# Lab11_445L.net
KiCad netlist of a schematic drawn in EAGLE
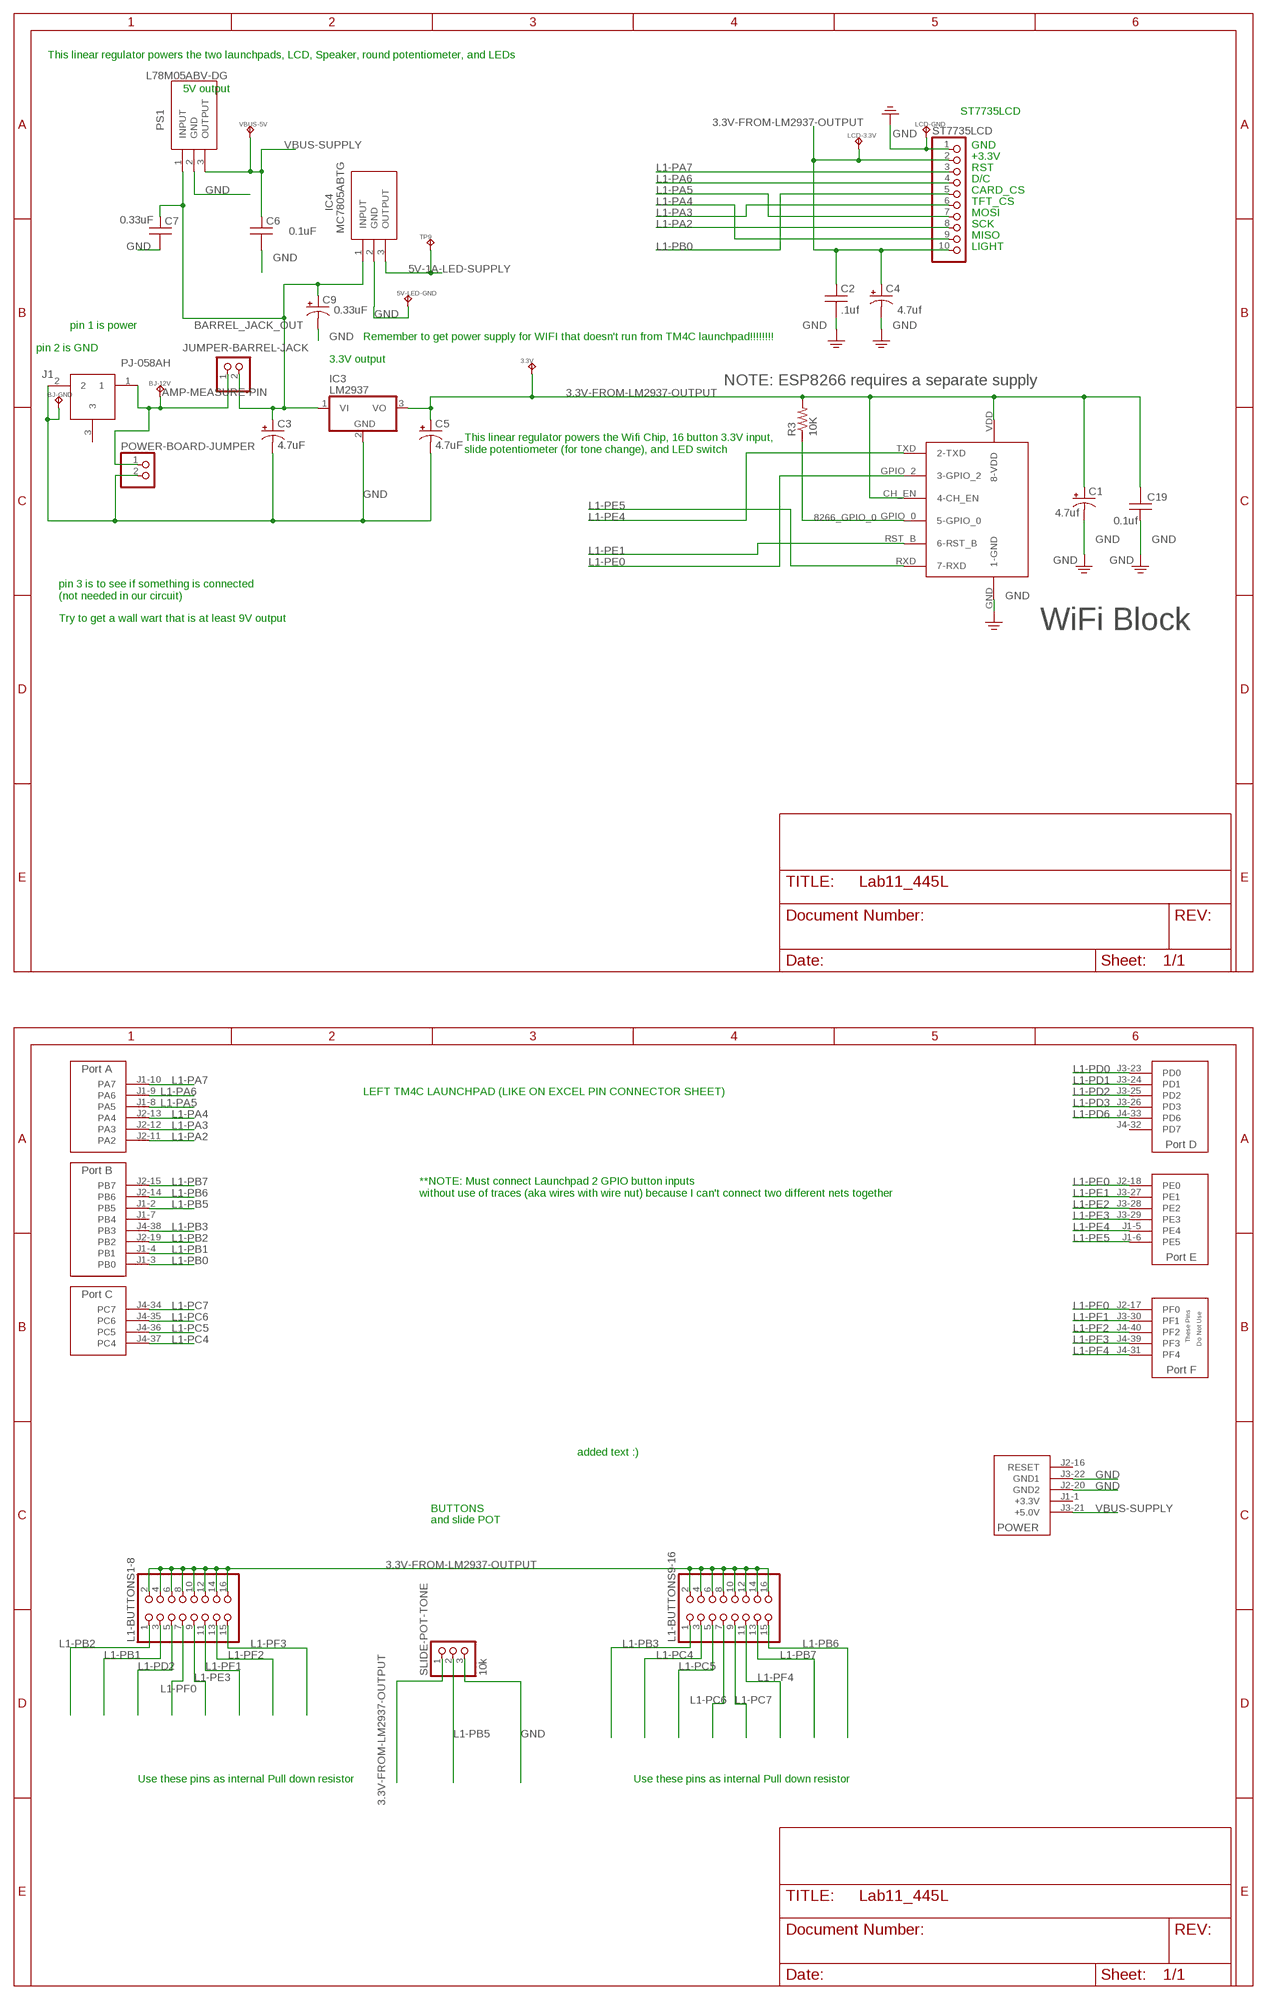
[diagram p0: schematic, sheet 1, part 1 of 2]
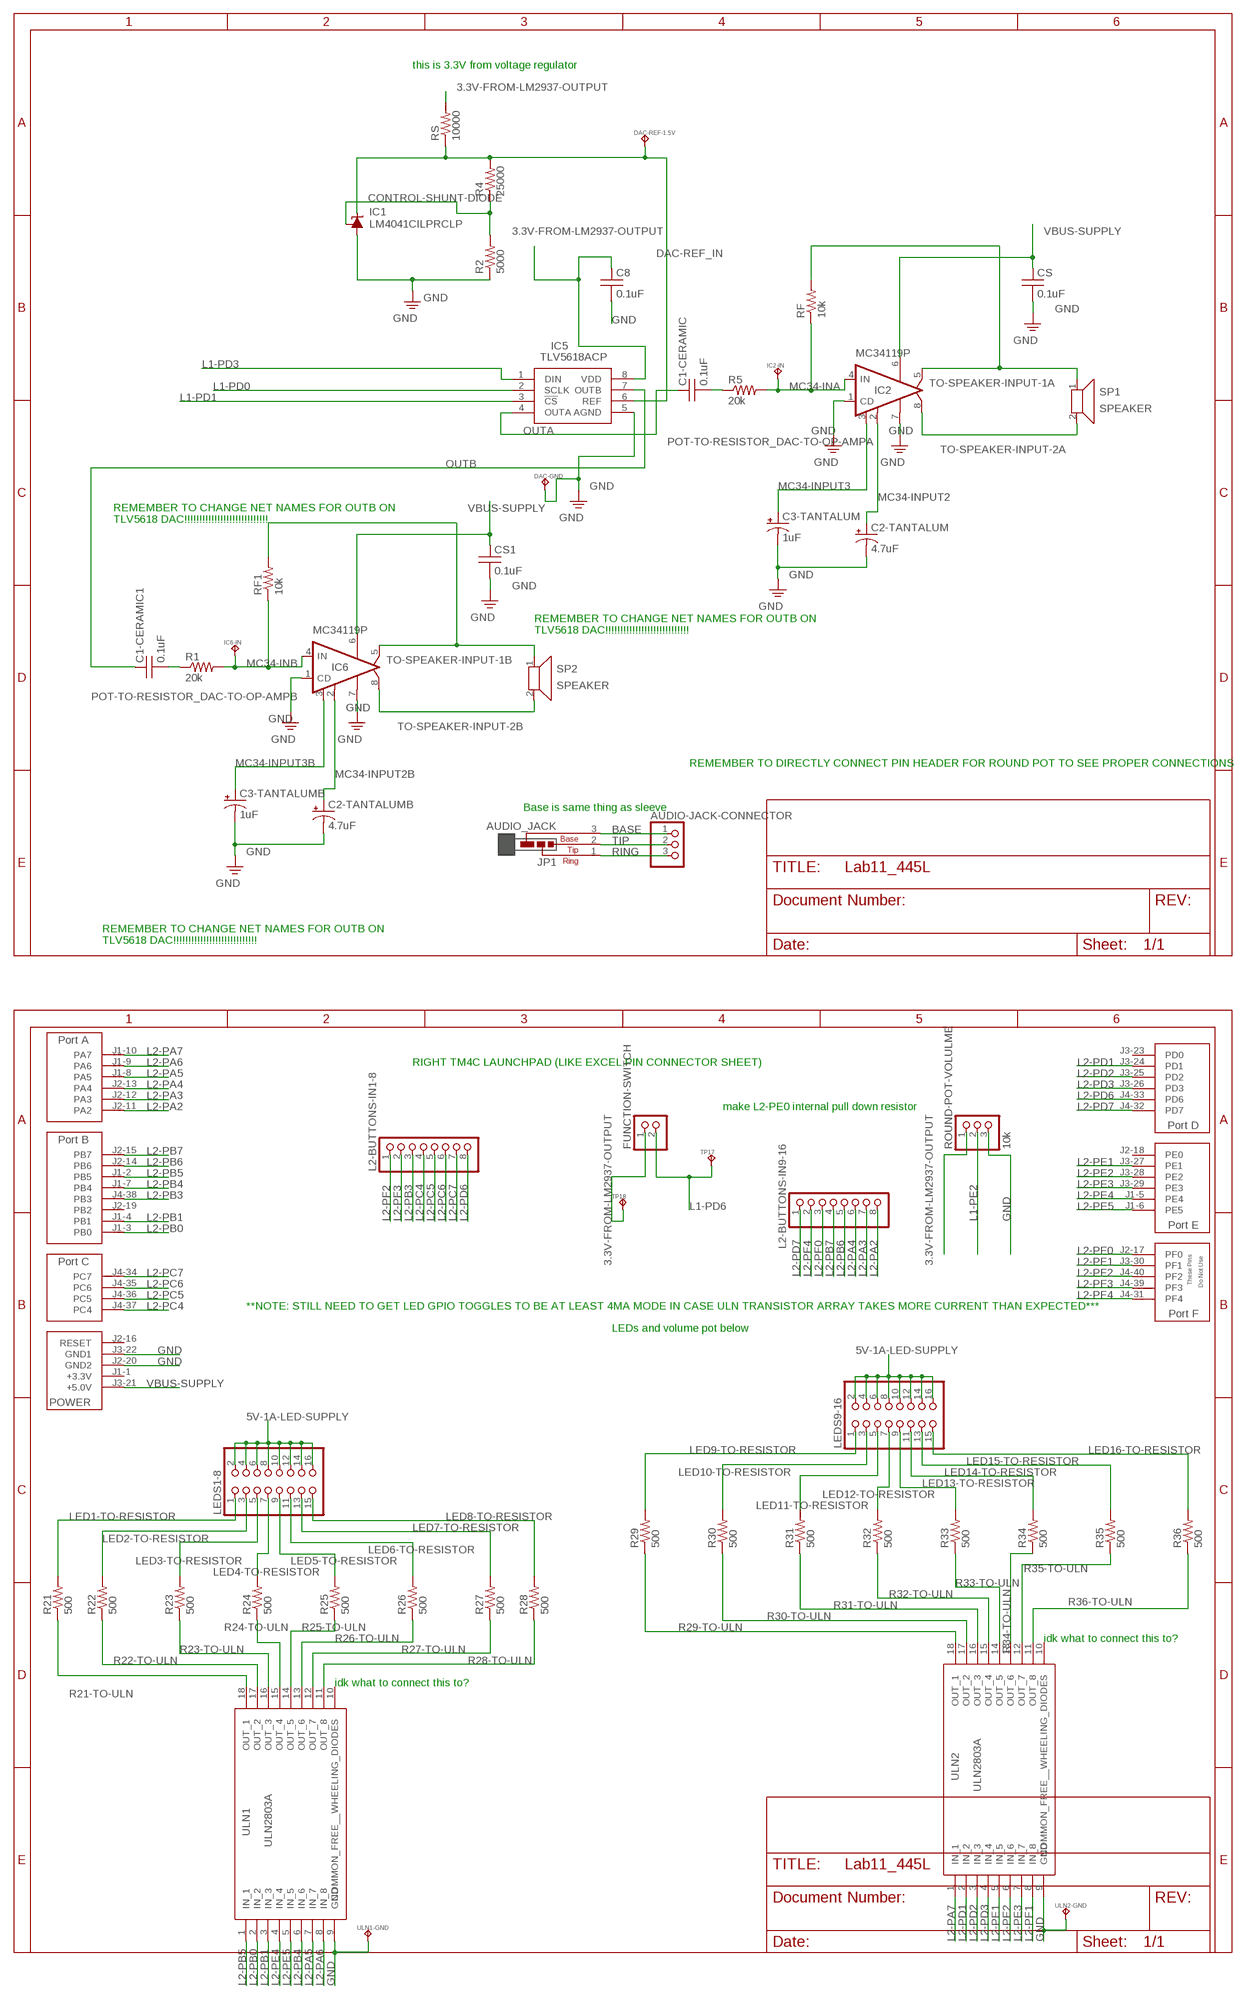
[diagram p1: schematic, sheet 1, part 2 of 2]

(export (version "E")
  (design (tool "Eeschema 10.0.6"))
  (components
    (comp (ref "3.3V")
      (value "TP_KEYSTONE500X")
      (footprint "eagle-import:P1.1MM")
      (libsource (lib "eagle-import") (part "TP_KEYSTONE500X"))
    )
    (comp (ref "5V-LED-GND")
      (value "TP_KEYSTONE500X")
      (footprint "eagle-import:P1.1MM")
      (libsource (lib "eagle-import") (part "TP_KEYSTONE500X"))
    )
    (comp (ref "AMP-MEASURE-PIN")
      (value "PINHD-1X2")
      (footprint "eagle-import:1X02")
      (libsource (lib "eagle-import") (part "PINHD-1X2"))
    )
    (comp (ref "AUDIO-JACK-CONNECTOR")
      (value "PINHD-1X3")
      (footprint "eagle-import:1X03")
      (libsource (lib "eagle-import") (part "PINHD-1X3"))
    )
    (comp (ref "BJ-12V")
      (value "TP_KEYSTONE500X")
      (footprint "eagle-import:P1.1MM")
      (libsource (lib "eagle-import") (part "TP_KEYSTONE500X"))
    )
    (comp (ref "BJ-GND")
      (value "TP_KEYSTONE500X")
      (footprint "eagle-import:P1.1MM")
      (libsource (lib "eagle-import") (part "TP_KEYSTONE500X"))
    )
    (comp (ref "C1")
      (value "4.7uf")
      (footprint "eagle-import:CAP200MILPOLARIZED")
      (libsource (lib "eagle-import") (part "CAPACITOR_POLARIZEDE5-6"))
    )
    (comp (ref "C1-CERAMIC")
      (value "0.1uF")
      (footprint "eagle-import:CAP100MIL")
      (libsource (lib "eagle-import") (part "CAPACITOR025-024X044"))
    )
    (comp (ref "C1-CERAMIC1")
      (value "0.1uF")
      (footprint "eagle-import:CAP100MIL")
      (libsource (lib "eagle-import") (part "CAPACITOR025-024X044"))
    )
    (comp (ref "C2")
      (value ".1uf")
      (footprint "eagle-import:CAP200MIL")
      (libsource (lib "eagle-import") (part "CAPACITOR050-024X044"))
    )
    (comp (ref "C2-TANTALUM")
      (value "4.7uF")
      (footprint "eagle-import:CAP200MILPOLARIZED")
      (libsource (lib "eagle-import") (part "CAPACITOR_POLARIZEDE5-6"))
    )
    (comp (ref "C2-TANTALUMB")
      (value "4.7uF")
      (footprint "eagle-import:CAP200MILPOLARIZED")
      (libsource (lib "eagle-import") (part "CAPACITOR_POLARIZEDE5-6"))
    )
    (comp (ref "C3")
      (value "4.7uF")
      (footprint "eagle-import:CAP200MILPOLARIZED")
      (libsource (lib "eagle-import") (part "CAPACITOR_POLARIZEDE5-6"))
    )
    (comp (ref "C3-TANTALUM")
      (value "1uF")
      (footprint "eagle-import:CAP200MILPOLARIZED")
      (libsource (lib "eagle-import") (part "CAPACITOR_POLARIZEDE5-6"))
    )
    (comp (ref "C3-TANTALUMB")
      (value "1uF")
      (footprint "eagle-import:CAP200MILPOLARIZED")
      (libsource (lib "eagle-import") (part "CAPACITOR_POLARIZEDE5-6"))
    )
    (comp (ref "C4")
      (value "4.7uf")
      (footprint "eagle-import:CAP200MILPOLARIZED")
      (libsource (lib "eagle-import") (part "CAPACITOR_POLARIZEDE5-6"))
    )
    (comp (ref "C5")
      (value "4.7uF")
      (footprint "eagle-import:CAP200MILPOLARIZED")
      (libsource (lib "eagle-import") (part "CAPACITOR_POLARIZEDE5-6"))
    )
    (comp (ref "C6")
      (value "0.1uF")
      (footprint "eagle-import:CAP200MIL")
      (libsource (lib "eagle-import") (part "CAPACITOR050-024X044"))
    )
    (comp (ref "C7")
      (value "0.33uF")
      (footprint "eagle-import:CAP200MIL")
      (libsource (lib "eagle-import") (part "CAPACITOR050-024X044"))
    )
    (comp (ref "C8")
      (value "0.1uF")
      (footprint "eagle-import:CAP100MIL")
      (libsource (lib "eagle-import") (part "CAPACITOR025-024X044"))
    )
    (comp (ref "C9")
      (value "0.33uF")
      (footprint "eagle-import:CAP200MILPOLARIZED")
      (libsource (lib "eagle-import") (part "CAPACITOR_POLARIZEDE5-6"))
    )
    (comp (ref "C19")
      (value "0.1uf")
      (footprint "eagle-import:CAP200MIL")
      (libsource (lib "eagle-import") (part "CAPACITOR050-024X044"))
    )
    (comp (ref "CS")
      (value "0.1uF")
      (footprint "eagle-import:CAP100MIL")
      (libsource (lib "eagle-import") (part "CAPACITOR025-024X044"))
    )
    (comp (ref "CS1")
      (value "0.1uF")
      (footprint "eagle-import:CAP100MIL")
      (libsource (lib "eagle-import") (part "CAPACITOR025-024X044"))
    )
    (comp (ref "DAC-GND")
      (value "TP_KEYSTONE500X")
      (footprint "eagle-import:P1.1MM")
      (libsource (lib "eagle-import") (part "TP_KEYSTONE500X"))
    )
    (comp (ref "DAC-REF-1.5V")
      (value "TP_KEYSTONE500X")
      (footprint "eagle-import:P1.1MM")
      (libsource (lib "eagle-import") (part "TP_KEYSTONE500X"))
    )
    (comp (ref "FUNCTION-SWITCH")
      (value "PINHD-1X2")
      (footprint "eagle-import:1X02")
      (libsource (lib "eagle-import") (part "PINHD-1X2"))
    )
    (comp (ref "IC1")
      (value "LM4041CILPRCLP")
      (footprint "eagle-import:LP_O-PBCY-W3")
      (fields (field (name "MPN") "LM4041CILP"))
      (libsource (lib "eagle-import") (part "LM4041CILPRLPC"))
    )
    (comp (ref "IC2")
      (value "MC34119P")
      (footprint "eagle-import:DIL08")
      (libsource (lib "eagle-import") (part "MC34119P"))
    )
    (comp (ref "IC2-IN")
      (value "TP_KEYSTONE500X")
      (footprint "eagle-import:P1.1MM")
      (libsource (lib "eagle-import") (part "TP_KEYSTONE500X"))
    )
    (comp (ref "IC3")
      (value "LM2937")
      (footprint "eagle-import:TO220")
      (libsource (lib "eagle-import") (part "LM2937"))
    )
    (comp (ref "IC4")
      (value "MC7805ABTG")
      (footprint "eagle-import:TO254P482X997X2018-3P")
      (fields (field (name "MOUSER_PART_NUMBER") "863-MC7805ABTG"))
      (libsource (lib "eagle-import") (part "MC7805ABTG"))
    )
    (comp (ref "IC5")
      (value "TLV5618ACP")
      (footprint "eagle-import:DIP794W53P254L959H508Q8N")
      (fields (field (name "MOUSER_PART_NUMBER") "595-TLV5618ACP"))
      (libsource (lib "eagle-import") (part "TLV5618ACP"))
    )
    (comp (ref "IC6")
      (value "MC34119P")
      (footprint "eagle-import:DIL08")
      (libsource (lib "eagle-import") (part "MC34119P"))
    )
    (comp (ref "IC6-IN")
      (value "TP_KEYSTONE500X")
      (footprint "eagle-import:P1.1MM")
      (libsource (lib "eagle-import") (part "TP_KEYSTONE500X"))
    )
    (comp (ref "J1")
      (value "PJ-058AH")
      (footprint "eagle-import:PJ058AH")
      (fields (field (name "MOUSER_PART_NUMBER") "490-PJ-058AH"))
      (libsource (lib "eagle-import") (part "PJ-058AH"))
    )
    (comp (ref "JP1")
      (value "AUDIO_JACK")
      (footprint "eagle-import:JACK")
      (libsource (lib "eagle-import") (part "AUDIO_JACK"))
    )
    (comp (ref "L1-BUTTONS1-8")
      (value "PINHD-2X8")
      (footprint "eagle-import:2X08")
      (libsource (lib "eagle-import") (part "PINHD-2X8"))
    )
    (comp (ref "L1-BUTTONS9-16")
      (value "PINHD-2X8")
      (footprint "eagle-import:2X08")
      (libsource (lib "eagle-import") (part "PINHD-2X8"))
    )
    (comp (ref "L2-BUTTONS-IN1-8")
      (value "PINHD-1X8")
      (footprint "eagle-import:1X08")
      (libsource (lib "eagle-import") (part "PINHD-1X8"))
    )
    (comp (ref "L2-BUTTONS-IN9-16")
      (value "PINHD-1X8")
      (footprint "eagle-import:1X08")
      (libsource (lib "eagle-import") (part "PINHD-1X8"))
    )
    (comp (ref "LCD-3.3V")
      (value "TP_KEYSTONE500X")
      (footprint "eagle-import:P1.1MM")
      (libsource (lib "eagle-import") (part "TP_KEYSTONE500X"))
    )
    (comp (ref "LCD-GND")
      (value "TP_KEYSTONE500X")
      (footprint "eagle-import:P1.1MM")
      (libsource (lib "eagle-import") (part "TP_KEYSTONE500X"))
    )
    (comp (ref "LEDS1-8")
      (value "PINHD-2X8")
      (footprint "eagle-import:2X08")
      (libsource (lib "eagle-import") (part "PINHD-2X8"))
    )
    (comp (ref "LEDS9-16")
      (value "PINHD-2X8")
      (footprint "eagle-import:2X08")
      (libsource (lib "eagle-import") (part "PINHD-2X8"))
    )
    (comp (ref "POWER-BOARD-JUMPER")
      (value "PINHD-1X2")
      (footprint "eagle-import:1X02")
      (libsource (lib "eagle-import") (part "PINHD-1X2"))
    )
    (comp (ref "PS1")
      (value "L78M05ABV-DG")
      (footprint "eagle-import:TO255P460X1020X2008-3P")
      (fields (field (name "MOUSER_PART_NUMBER") "511-L78M05ABV-DG"))
      (libsource (lib "eagle-import") (part "L78M05ABV-DG"))
    )
    (comp (ref "R1")
      (value "20k")
      (footprint "eagle-import:RES200MIL")
      (libsource (lib "eagle-import") (part "RESISTOR0204/5"))
    )
    (comp (ref "R2")
      (value "5000")
      (footprint "eagle-import:RES200MIL")
      (libsource (lib "eagle-import") (part "RESISTOR0204/5"))
    )
    (comp (ref "R3")
      (value "10K")
      (footprint "eagle-import:RES300MIL")
      (libsource (lib "eagle-import") (part "RESISTOR0204/7"))
    )
    (comp (ref "R4")
      (value "25000")
      (footprint "eagle-import:RES200MIL")
      (libsource (lib "eagle-import") (part "RESISTOR0204/5"))
    )
    (comp (ref "R5")
      (value "20k")
      (footprint "eagle-import:RES200MIL")
      (libsource (lib "eagle-import") (part "RESISTOR0204/5"))
    )
    (comp (ref "R21")
      (value "500")
      (footprint "eagle-import:RES300MIL")
      (libsource (lib "eagle-import") (part "RESISTOR0204/7"))
    )
    (comp (ref "R22")
      (value "500")
      (footprint "eagle-import:RES300MIL")
      (libsource (lib "eagle-import") (part "RESISTOR0204/7"))
    )
    (comp (ref "R23")
      (value "500")
      (footprint "eagle-import:RES300MIL")
      (libsource (lib "eagle-import") (part "RESISTOR0204/7"))
    )
    (comp (ref "R24")
      (value "500")
      (footprint "eagle-import:RES300MIL")
      (libsource (lib "eagle-import") (part "RESISTOR0204/7"))
    )
    (comp (ref "R25")
      (value "500")
      (footprint "eagle-import:RES300MIL")
      (libsource (lib "eagle-import") (part "RESISTOR0204/7"))
    )
    (comp (ref "R26")
      (value "500")
      (footprint "eagle-import:RES300MIL")
      (libsource (lib "eagle-import") (part "RESISTOR0204/7"))
    )
    (comp (ref "R27")
      (value "500")
      (footprint "eagle-import:RES300MIL")
      (libsource (lib "eagle-import") (part "RESISTOR0204/7"))
    )
    (comp (ref "R28")
      (value "500")
      (footprint "eagle-import:RES300MIL")
      (libsource (lib "eagle-import") (part "RESISTOR0204/7"))
    )
    (comp (ref "R29")
      (value "500")
      (footprint "eagle-import:RES300MIL")
      (libsource (lib "eagle-import") (part "RESISTOR0204/7"))
    )
    (comp (ref "R30")
      (value "500")
      (footprint "eagle-import:RES300MIL")
      (libsource (lib "eagle-import") (part "RESISTOR0204/7"))
    )
    (comp (ref "R31")
      (value "500")
      (footprint "eagle-import:RES300MIL")
      (libsource (lib "eagle-import") (part "RESISTOR0204/7"))
    )
    (comp (ref "R32")
      (value "500")
      (footprint "eagle-import:RES300MIL")
      (libsource (lib "eagle-import") (part "RESISTOR0204/7"))
    )
    (comp (ref "R33")
      (value "500")
      (footprint "eagle-import:RES300MIL")
      (libsource (lib "eagle-import") (part "RESISTOR0204/7"))
    )
    (comp (ref "R34")
      (value "500")
      (footprint "eagle-import:RES300MIL")
      (libsource (lib "eagle-import") (part "RESISTOR0204/7"))
    )
    (comp (ref "R35")
      (value "500")
      (footprint "eagle-import:RES300MIL")
      (libsource (lib "eagle-import") (part "RESISTOR0204/7"))
    )
    (comp (ref "R36")
      (value "500")
      (footprint "eagle-import:RES300MIL")
      (libsource (lib "eagle-import") (part "RESISTOR0204/7"))
    )
    (comp (ref "RF")
      (value "10k")
      (footprint "eagle-import:RES200MIL")
      (libsource (lib "eagle-import") (part "RESISTOR0204/5"))
    )
    (comp (ref "RF1")
      (value "10k")
      (footprint "eagle-import:RES200MIL")
      (libsource (lib "eagle-import") (part "RESISTOR0204/5"))
    )
    (comp (ref "ROUND-POT-VOLULME")
      (value "10k")
      (footprint "eagle-import:1X03")
      (libsource (lib "eagle-import") (part "PINHD-1X3"))
    )
    (comp (ref "RS")
      (value "10000")
      (footprint "eagle-import:RES200MIL")
      (libsource (lib "eagle-import") (part "RESISTOR0204/5"))
    )
    (comp (ref "SLIDE-POT-TONE")
      (value "10k")
      (footprint "eagle-import:1X03")
      (libsource (lib "eagle-import") (part "PINHD-1X3"))
    )
    (comp (ref "SP1")
      (value "SPEAKER")
      (footprint "eagle-import:1X02")
      (libsource (lib "eagle-import") (part "SPEAKER"))
    )
    (comp (ref "SP2")
      (value "SPEAKER")
      (footprint "eagle-import:1X02")
      (libsource (lib "eagle-import") (part "SPEAKER"))
    )
    (comp (ref "ST7735LCD")
      (value "PINHD-1X10")
      (footprint "eagle-import:1X10")
      (libsource (lib "eagle-import") (part "PINHD-1X10"))
    )
    (comp (ref "TP9")
      (value "TP_KEYSTONE500X")
      (footprint "eagle-import:P1.1MM")
      (libsource (lib "eagle-import") (part "TP_KEYSTONE500X"))
    )
    (comp (ref "TP17")
      (value "TP_KEYSTONE500X")
      (footprint "eagle-import:P1.1MM")
      (libsource (lib "eagle-import") (part "TP_KEYSTONE500X"))
    )
    (comp (ref "TP18")
      (value "TP_KEYSTONE500X")
      (footprint "eagle-import:P1.1MM")
      (libsource (lib "eagle-import") (part "TP_KEYSTONE500X"))
    )
    (comp (ref "U$1")
      (value "ESP_8266")
      (footprint "eagle-import:ESP8266")
      (libsource (lib "eagle-import") (part "ESP_8266"))
    )
    (comp (ref "U$2")
      (value "TM4C_BP")
      (footprint "eagle-import:TM4C_BOOSTER_PACK")
      (libsource (lib "eagle-import") (part "TM4C_BP"))
    )
    (comp (ref "U$3")
      (value "TM4C_BP")
      (footprint "eagle-import:TM4C_BOOSTER_PACK")
      (libsource (lib "eagle-import") (part "TM4C_BP"))
    )
    (comp (ref "ULN1")
      (value "ULN2803A")
      (footprint "eagle-import:DIP850W46P254L2324H393Q18N")
      (fields (field (name "MOUSER_PART_NUMBER") "511-ULN2803A"))
      (libsource (lib "eagle-import") (part "ULN2803A"))
    )
    (comp (ref "ULN1-GND")
      (value "TP_KEYSTONE500X")
      (footprint "eagle-import:P1.1MM")
      (libsource (lib "eagle-import") (part "TP_KEYSTONE500X"))
    )
    (comp (ref "ULN2")
      (value "ULN2803A")
      (footprint "eagle-import:DIP850W46P254L2324H393Q18N")
      (fields (field (name "MOUSER_PART_NUMBER") "511-ULN2803A"))
      (libsource (lib "eagle-import") (part "ULN2803A"))
    )
    (comp (ref "ULN2-GND")
      (value "TP_KEYSTONE500X")
      (footprint "eagle-import:P1.1MM")
      (libsource (lib "eagle-import") (part "TP_KEYSTONE500X"))
    )
    (comp (ref "VBUS-5V")
      (value "TP_KEYSTONE500X")
      (footprint "eagle-import:P1.1MM")
      (libsource (lib "eagle-import") (part "TP_KEYSTONE500X"))
    )
  )
  (nets
    (net (code "1") (name "/3.3V-FROM-LM2937-OUTPUT") (class "Default")
      (node (ref "3.3V") (pin "TP") (pinfunction "TP_TP") (pintype "input"))
      (node (ref "C1") (pin "+") (pinfunction "+_+") (pintype "passive"))
      (node (ref "C19") (pin "2") (pinfunction "2_2") (pintype "passive"))
      (node (ref "C2") (pin "1") (pinfunction "1_1") (pintype "passive"))
      (node (ref "C4") (pin "+") (pinfunction "+_+") (pintype "passive"))
      (node (ref "C5") (pin "+") (pinfunction "+_+") (pintype "passive"))
      (node (ref "C8") (pin "1") (pinfunction "1_1") (pintype "passive"))
      (node (ref "FUNCTION-SWITCH") (pin "1") (pinfunction "1_1") (pintype "passive"))
      (node (ref "IC3") (pin "3") (pinfunction "VO_3") (pintype "passive"))
      (node (ref "IC5") (pin "8") (pinfunction "VDD_8") (pintype "bidirectional"))
      (node (ref "L1-BUTTONS1-8") (pin "10") (pinfunction "10_10") (pintype "passive"))
      (node (ref "L1-BUTTONS1-8") (pin "12") (pinfunction "12_12") (pintype "passive"))
      (node (ref "L1-BUTTONS1-8") (pin "14") (pinfunction "14_14") (pintype "passive"))
      (node (ref "L1-BUTTONS1-8") (pin "16") (pinfunction "16_16") (pintype "passive"))
      (node (ref "L1-BUTTONS1-8") (pin "2") (pinfunction "2_2") (pintype "passive"))
      (node (ref "L1-BUTTONS1-8") (pin "4") (pinfunction "4_4") (pintype "passive"))
      (node (ref "L1-BUTTONS1-8") (pin "6") (pinfunction "6_6") (pintype "passive"))
      (node (ref "L1-BUTTONS1-8") (pin "8") (pinfunction "8_8") (pintype "passive"))
      (node (ref "L1-BUTTONS9-16") (pin "10") (pinfunction "10_10") (pintype "passive"))
      (node (ref "L1-BUTTONS9-16") (pin "12") (pinfunction "12_12") (pintype "passive"))
      (node (ref "L1-BUTTONS9-16") (pin "14") (pinfunction "14_14") (pintype "passive"))
      (node (ref "L1-BUTTONS9-16") (pin "16") (pinfunction "16_16") (pintype "passive"))
      (node (ref "L1-BUTTONS9-16") (pin "2") (pinfunction "2_2") (pintype "passive"))
      (node (ref "L1-BUTTONS9-16") (pin "4") (pinfunction "4_4") (pintype "passive"))
      (node (ref "L1-BUTTONS9-16") (pin "6") (pinfunction "6_6") (pintype "passive"))
      (node (ref "L1-BUTTONS9-16") (pin "8") (pinfunction "8_8") (pintype "passive"))
      (node (ref "LCD-3.3V") (pin "TP") (pinfunction "TP_TP") (pintype "input"))
      (node (ref "R3") (pin "2") (pinfunction "2_2") (pintype "passive"))
      (node (ref "ROUND-POT-VOLULME") (pin "1") (pinfunction "1_1") (pintype "passive"))
      (node (ref "RS") (pin "2") (pinfunction "2_2") (pintype "passive"))
      (node (ref "SLIDE-POT-TONE") (pin "1") (pinfunction "1_1") (pintype "passive"))
      (node (ref "ST7735LCD") (pin "10") (pinfunction "10_10") (pintype "passive"))
      (node (ref "ST7735LCD") (pin "2") (pinfunction "2_2") (pintype "passive"))
      (node (ref "TP18") (pin "TP") (pinfunction "TP_TP") (pintype "input"))
      (node (ref "U$1") (pin "CH_EN") (pinfunction "4-CH_EN_CH_EN") (pintype "bidirectional"))
      (node (ref "U$1") (pin "VDD") (pinfunction "8-VDD_VDD") (pintype "bidirectional"))
    )
    (net (code "2") (name "/5V-1A-LED-SUPPLY") (class "Default")
      (node (ref "IC4") (pin "3") (pinfunction "OUTPUT_3") (pintype "output"))
      (node (ref "LEDS1-8") (pin "10") (pinfunction "10_10") (pintype "passive"))
      (node (ref "LEDS1-8") (pin "12") (pinfunction "12_12") (pintype "passive"))
      (node (ref "LEDS1-8") (pin "14") (pinfunction "14_14") (pintype "passive"))
      (node (ref "LEDS1-8") (pin "16") (pinfunction "16_16") (pintype "passive"))
      (node (ref "LEDS1-8") (pin "2") (pinfunction "2_2") (pintype "passive"))
      (node (ref "LEDS1-8") (pin "4") (pinfunction "4_4") (pintype "passive"))
      (node (ref "LEDS1-8") (pin "6") (pinfunction "6_6") (pintype "passive"))
      (node (ref "LEDS1-8") (pin "8") (pinfunction "8_8") (pintype "passive"))
      (node (ref "LEDS9-16") (pin "10") (pinfunction "10_10") (pintype "passive"))
      (node (ref "LEDS9-16") (pin "12") (pinfunction "12_12") (pintype "passive"))
      (node (ref "LEDS9-16") (pin "14") (pinfunction "14_14") (pintype "passive"))
      (node (ref "LEDS9-16") (pin "16") (pinfunction "16_16") (pintype "passive"))
      (node (ref "LEDS9-16") (pin "2") (pinfunction "2_2") (pintype "passive"))
      (node (ref "LEDS9-16") (pin "4") (pinfunction "4_4") (pintype "passive"))
      (node (ref "LEDS9-16") (pin "6") (pinfunction "6_6") (pintype "passive"))
      (node (ref "LEDS9-16") (pin "8") (pinfunction "8_8") (pintype "passive"))
      (node (ref "TP9") (pin "TP") (pinfunction "TP_TP") (pintype "input"))
    )
    (net (code "3") (name "/8266_GPIO_0") (class "Default")
      (node (ref "R3") (pin "1") (pinfunction "1_1") (pintype "passive"))
      (node (ref "U$1") (pin "GPIO_0") (pinfunction "5-GPIO_0_GPIO_0") (pintype "bidirectional"))
    )
    (net (code "4") (name "/BARREL_JACK_OUT") (class "Default")
      (node (ref "AMP-MEASURE-PIN") (pin "1") (pinfunction "1_1") (pintype "passive"))
      (node (ref "BJ-12V") (pin "TP") (pinfunction "TP_TP") (pintype "input"))
      (node (ref "J1") (pin "1") (pinfunction "1_1") (pintype "bidirectional"))
      (node (ref "POWER-BOARD-JUMPER") (pin "1") (pinfunction "1_1") (pintype "passive"))
    )
    (net (code "5") (name "/BASE") (class "Default")
      (node (ref "AUDIO-JACK-CONNECTOR") (pin "1") (pinfunction "1_1") (pintype "passive"))
      (node (ref "JP1") (pin "3") (pinfunction "BASE_3") (pintype "passive"))
    )
    (net (code "6") (name "/CONTROL-SHUNT-DIODE") (class "Default")
      (node (ref "IC1") (pin "1") (pinfunction "FB_1") (pintype "passive"))
      (node (ref "R2") (pin "2") (pinfunction "2_2") (pintype "passive"))
      (node (ref "R4") (pin "1") (pinfunction "1_1") (pintype "passive"))
    )
    (net (code "7") (name "/DAC-REF_IN") (class "Default")
      (node (ref "DAC-REF-1.5V") (pin "TP") (pinfunction "TP_TP") (pintype "input"))
      (node (ref "IC1") (pin "2") (pinfunction "C_2") (pintype "passive"))
      (node (ref "IC5") (pin "6") (pinfunction "REF_6") (pintype "bidirectional"))
      (node (ref "R4") (pin "2") (pinfunction "2_2") (pintype "passive"))
      (node (ref "RS") (pin "1") (pinfunction "1_1") (pintype "passive"))
    )
    (net (code "8") (name "/JUMPER-BARREL-JACK") (class "Default")
      (node (ref "AMP-MEASURE-PIN") (pin "2") (pinfunction "2_2") (pintype "passive"))
      (node (ref "C3") (pin "+") (pinfunction "+_+") (pintype "passive"))
      (node (ref "C7") (pin "1") (pinfunction "1_1") (pintype "passive"))
      (node (ref "C9") (pin "+") (pinfunction "+_+") (pintype "passive"))
      (node (ref "IC3") (pin "1") (pinfunction "VI_1") (pintype "input"))
      (node (ref "IC4") (pin "1") (pinfunction "INPUT_1") (pintype "input"))
      (node (ref "PS1") (pin "1") (pinfunction "INPUT_1") (pintype "input"))
    )
    (net (code "9") (name "/L1-PA2") (class "Default")
      (node (ref "ST7735LCD") (pin "8") (pinfunction "8_8") (pintype "passive"))
      (node (ref "U$2") (pin "J2-11") (pinfunction "PA2_J2-11") (pintype "bidirectional"))
    )
    (net (code "10") (name "/L1-PA3") (class "Default")
      (node (ref "ST7735LCD") (pin "6") (pinfunction "6_6") (pintype "passive"))
      (node (ref "U$2") (pin "J2-12") (pinfunction "PA3_J2-12") (pintype "bidirectional"))
    )
    (net (code "11") (name "/L1-PA4") (class "Default")
      (node (ref "ST7735LCD") (pin "9") (pinfunction "9_9") (pintype "passive"))
      (node (ref "U$2") (pin "J2-13") (pinfunction "PA4_J2-13") (pintype "bidirectional"))
    )
    (net (code "12") (name "/L1-PA5") (class "Default")
      (node (ref "ST7735LCD") (pin "7") (pinfunction "7_7") (pintype "passive"))
      (node (ref "U$2") (pin "J1-8") (pinfunction "PA5_J1-8") (pintype "bidirectional"))
    )
    (net (code "13") (name "/L1-PA6") (class "Default")
      (node (ref "ST7735LCD") (pin "4") (pinfunction "4_4") (pintype "passive"))
      (node (ref "U$2") (pin "J1-9") (pinfunction "PA6_J1-9") (pintype "bidirectional"))
    )
    (net (code "14") (name "/L1-PA7") (class "Default")
      (node (ref "ST7735LCD") (pin "3") (pinfunction "3_3") (pintype "passive"))
      (node (ref "U$2") (pin "J1-10") (pinfunction "PA7_J1-10") (pintype "bidirectional"))
    )
    (net (code "15") (name "/L1-PB0") (class "Default")
      (node (ref "ST7735LCD") (pin "5") (pinfunction "5_5") (pintype "passive"))
      (node (ref "U$2") (pin "J1-3") (pinfunction "PB0_J1-3") (pintype "bidirectional"))
    )
    (net (code "16") (name "/L1-PB1") (class "Default")
      (node (ref "L1-BUTTONS1-8") (pin "3") (pinfunction "3_3") (pintype "passive"))
      (node (ref "U$2") (pin "J1-4") (pinfunction "PB1_J1-4") (pintype "bidirectional"))
    )
    (net (code "17") (name "/L1-PB2") (class "Default")
      (node (ref "L1-BUTTONS1-8") (pin "1") (pinfunction "1_1") (pintype "passive"))
      (node (ref "U$2") (pin "J2-19") (pinfunction "PB2_J2-19") (pintype "bidirectional"))
    )
    (net (code "18") (name "/L1-PB3") (class "Default")
      (node (ref "L1-BUTTONS9-16") (pin "1") (pinfunction "1_1") (pintype "passive"))
      (node (ref "U$2") (pin "J4-38") (pinfunction "PB3_J4-38") (pintype "bidirectional"))
    )
    (net (code "19") (name "/L1-PB5") (class "Default")
      (node (ref "SLIDE-POT-TONE") (pin "2") (pinfunction "2_2") (pintype "passive"))
      (node (ref "U$2") (pin "J1-2") (pinfunction "PB5_J1-2") (pintype "bidirectional"))
    )
    (net (code "20") (name "/L1-PB6") (class "Default")
      (node (ref "L1-BUTTONS9-16") (pin "15") (pinfunction "15_15") (pintype "passive"))
      (node (ref "U$2") (pin "J2-14") (pinfunction "PB6_J2-14") (pintype "bidirectional"))
    )
    (net (code "21") (name "/L1-PB7") (class "Default")
      (node (ref "L1-BUTTONS9-16") (pin "13") (pinfunction "13_13") (pintype "passive"))
      (node (ref "U$2") (pin "J2-15") (pinfunction "PB7_J2-15") (pintype "bidirectional"))
    )
    (net (code "22") (name "/L1-PC4") (class "Default")
      (node (ref "L1-BUTTONS9-16") (pin "3") (pinfunction "3_3") (pintype "passive"))
      (node (ref "U$2") (pin "J4-37") (pinfunction "PC4_J4-37") (pintype "bidirectional"))
    )
    (net (code "23") (name "/L1-PC5") (class "Default")
      (node (ref "L1-BUTTONS9-16") (pin "5") (pinfunction "5_5") (pintype "passive"))
      (node (ref "U$2") (pin "J4-36") (pinfunction "PC5_J4-36") (pintype "bidirectional"))
    )
    (net (code "24") (name "/L1-PC6") (class "Default")
      (node (ref "L1-BUTTONS9-16") (pin "7") (pinfunction "7_7") (pintype "passive"))
      (node (ref "U$2") (pin "J4-35") (pinfunction "PC6_J4-35") (pintype "bidirectional"))
    )
    (net (code "25") (name "/L1-PC7") (class "Default")
      (node (ref "L1-BUTTONS9-16") (pin "9") (pinfunction "9_9") (pintype "passive"))
      (node (ref "U$2") (pin "J4-34") (pinfunction "PC7_J4-34") (pintype "bidirectional"))
    )
    (net (code "26") (name "/L1-PD0") (class "Default")
      (node (ref "IC5") (pin "2") (pinfunction "SCLK_2") (pintype "bidirectional"))
      (node (ref "U$2") (pin "J3-23") (pinfunction "PD0_J3-23") (pintype "bidirectional"))
    )
    (net (code "27") (name "/L1-PD1") (class "Default")
      (node (ref "IC5") (pin "3") (pinfunction "~{CS}_3") (pintype "bidirectional"))
      (node (ref "U$2") (pin "J3-24") (pinfunction "PD1_J3-24") (pintype "bidirectional"))
    )
    (net (code "28") (name "/L1-PD2") (class "Default")
      (node (ref "L1-BUTTONS1-8") (pin "5") (pinfunction "5_5") (pintype "passive"))
      (node (ref "U$2") (pin "J3-25") (pinfunction "PD2_J3-25") (pintype "bidirectional"))
    )
    (net (code "29") (name "/L1-PD3") (class "Default")
      (node (ref "IC5") (pin "1") (pinfunction "DIN_1") (pintype "bidirectional"))
      (node (ref "U$2") (pin "J3-26") (pinfunction "PD3_J3-26") (pintype "bidirectional"))
    )
    (net (code "30") (name "/L1-PD6") (class "Default")
      (node (ref "FUNCTION-SWITCH") (pin "2") (pinfunction "2_2") (pintype "passive"))
      (node (ref "TP17") (pin "TP") (pinfunction "TP_TP") (pintype "input"))
      (node (ref "U$2") (pin "J4-33") (pinfunction "PD6_J4-33") (pintype "bidirectional"))
    )
    (net (code "31") (name "/L1-PE0") (class "Default")
      (node (ref "U$1") (pin "GPIO_2") (pinfunction "3-GPIO_2_GPIO_2") (pintype "bidirectional"))
      (node (ref "U$2") (pin "J2-18") (pinfunction "PE0_J2-18") (pintype "bidirectional"))
    )
    (net (code "32") (name "/L1-PE1") (class "Default")
      (node (ref "U$1") (pin "RST_B") (pinfunction "6-RST_B_RST_B") (pintype "bidirectional"))
      (node (ref "U$2") (pin "J3-27") (pinfunction "PE1_J3-27") (pintype "bidirectional"))
    )
    (net (code "33") (name "/L1-PE2") (class "Default")
      (node (ref "ROUND-POT-VOLULME") (pin "2") (pinfunction "2_2") (pintype "passive"))
      (node (ref "U$2") (pin "J3-28") (pinfunction "PE2_J3-28") (pintype "bidirectional"))
    )
    (net (code "34") (name "/L1-PE3") (class "Default")
      (node (ref "L1-BUTTONS1-8") (pin "9") (pinfunction "9_9") (pintype "passive"))
      (node (ref "U$2") (pin "J3-29") (pinfunction "PE3_J3-29") (pintype "bidirectional"))
    )
    (net (code "35") (name "/L1-PE4") (class "Default")
      (node (ref "U$1") (pin "TXD") (pinfunction "2-TXD_TXD") (pintype "bidirectional"))
      (node (ref "U$2") (pin "J1-5") (pinfunction "PE4_J1-5") (pintype "bidirectional"))
    )
    (net (code "36") (name "/L1-PE5") (class "Default")
      (node (ref "U$1") (pin "RXD") (pinfunction "7-RXD_RXD") (pintype "bidirectional"))
      (node (ref "U$2") (pin "J1-6") (pinfunction "PE5_J1-6") (pintype "bidirectional"))
    )
    (net (code "37") (name "/L1-PF0") (class "Default")
      (node (ref "L1-BUTTONS1-8") (pin "7") (pinfunction "7_7") (pintype "passive"))
      (node (ref "U$2") (pin "J2-17") (pinfunction "PF0_J2-17") (pintype "bidirectional"))
    )
    (net (code "38") (name "/L1-PF1") (class "Default")
      (node (ref "L1-BUTTONS1-8") (pin "11") (pinfunction "11_11") (pintype "passive"))
      (node (ref "U$2") (pin "J3-30") (pinfunction "PF1_J3-30") (pintype "bidirectional"))
    )
    (net (code "39") (name "/L1-PF2") (class "Default")
      (node (ref "L1-BUTTONS1-8") (pin "13") (pinfunction "13_13") (pintype "passive"))
      (node (ref "U$2") (pin "J4-40") (pinfunction "PF2_J4-40") (pintype "bidirectional"))
    )
    (net (code "40") (name "/L1-PF3") (class "Default")
      (node (ref "L1-BUTTONS1-8") (pin "15") (pinfunction "15_15") (pintype "passive"))
      (node (ref "U$2") (pin "J4-39") (pinfunction "PF3_J4-39") (pintype "bidirectional"))
    )
    (net (code "41") (name "/L1-PF4") (class "Default")
      (node (ref "L1-BUTTONS9-16") (pin "11") (pinfunction "11_11") (pintype "passive"))
      (node (ref "U$2") (pin "J4-31") (pinfunction "PF4_J4-31") (pintype "bidirectional"))
    )
    (net (code "42") (name "/L2-PA2") (class "Default")
      (node (ref "L2-BUTTONS-IN9-16") (pin "8") (pinfunction "8_8") (pintype "passive"))
      (node (ref "U$3") (pin "J2-11") (pinfunction "PA2_J2-11") (pintype "bidirectional"))
    )
    (net (code "43") (name "/L2-PA3") (class "Default")
      (node (ref "L2-BUTTONS-IN9-16") (pin "7") (pinfunction "7_7") (pintype "passive"))
      (node (ref "U$3") (pin "J2-12") (pinfunction "PA3_J2-12") (pintype "bidirectional"))
    )
    (net (code "44") (name "/L2-PA4") (class "Default")
      (node (ref "L2-BUTTONS-IN9-16") (pin "6") (pinfunction "6_6") (pintype "passive"))
      (node (ref "U$3") (pin "J2-13") (pinfunction "PA4_J2-13") (pintype "bidirectional"))
    )
    (net (code "45") (name "/L2-PA5") (class "Default")
      (node (ref "U$3") (pin "J1-8") (pinfunction "PA5_J1-8") (pintype "bidirectional"))
      (node (ref "ULN1") (pin "7") (pinfunction "IN_7_7") (pintype "bidirectional"))
    )
    (net (code "46") (name "/L2-PA6") (class "Default")
      (node (ref "U$3") (pin "J1-9") (pinfunction "PA6_J1-9") (pintype "bidirectional"))
      (node (ref "ULN1") (pin "8") (pinfunction "IN_8_8") (pintype "bidirectional"))
    )
    (net (code "47") (name "/L2-PA7") (class "Default")
      (node (ref "U$3") (pin "J1-10") (pinfunction "PA7_J1-10") (pintype "bidirectional"))
      (node (ref "ULN2") (pin "1") (pinfunction "IN_1_1") (pintype "bidirectional"))
    )
    (net (code "48") (name "/L2-PB0") (class "Default")
      (node (ref "U$3") (pin "J1-3") (pinfunction "PB0_J1-3") (pintype "bidirectional"))
      (node (ref "ULN1") (pin "2") (pinfunction "IN_2_2") (pintype "bidirectional"))
    )
    (net (code "49") (name "/L2-PB1") (class "Default")
      (node (ref "U$3") (pin "J1-4") (pinfunction "PB1_J1-4") (pintype "bidirectional"))
      (node (ref "ULN1") (pin "3") (pinfunction "IN_3_3") (pintype "bidirectional"))
    )
    (net (code "50") (name "/L2-PB3") (class "Default")
      (node (ref "L2-BUTTONS-IN1-8") (pin "3") (pinfunction "3_3") (pintype "passive"))
      (node (ref "U$3") (pin "J4-38") (pinfunction "PB3_J4-38") (pintype "bidirectional"))
    )
    (net (code "51") (name "/L2-PB4") (class "Default")
      (node (ref "U$3") (pin "J1-7") (pinfunction "PB4_J1-7") (pintype "bidirectional"))
      (node (ref "ULN1") (pin "6") (pinfunction "IN_6_6") (pintype "bidirectional"))
    )
    (net (code "52") (name "/L2-PB5") (class "Default")
      (node (ref "U$3") (pin "J1-2") (pinfunction "PB5_J1-2") (pintype "bidirectional"))
      (node (ref "ULN1") (pin "1") (pinfunction "IN_1_1") (pintype "bidirectional"))
    )
    (net (code "53") (name "/L2-PB6") (class "Default")
      (node (ref "L2-BUTTONS-IN9-16") (pin "5") (pinfunction "5_5") (pintype "passive"))
      (node (ref "U$3") (pin "J2-14") (pinfunction "PB6_J2-14") (pintype "bidirectional"))
    )
    (net (code "54") (name "/L2-PB7") (class "Default")
      (node (ref "L2-BUTTONS-IN9-16") (pin "4") (pinfunction "4_4") (pintype "passive"))
      (node (ref "U$3") (pin "J2-15") (pinfunction "PB7_J2-15") (pintype "bidirectional"))
    )
    (net (code "55") (name "/L2-PC4") (class "Default")
      (node (ref "L2-BUTTONS-IN1-8") (pin "4") (pinfunction "4_4") (pintype "passive"))
      (node (ref "U$3") (pin "J4-37") (pinfunction "PC4_J4-37") (pintype "bidirectional"))
    )
    (net (code "56") (name "/L2-PC5") (class "Default")
      (node (ref "L2-BUTTONS-IN1-8") (pin "5") (pinfunction "5_5") (pintype "passive"))
      (node (ref "U$3") (pin "J4-36") (pinfunction "PC5_J4-36") (pintype "bidirectional"))
    )
    (net (code "57") (name "/L2-PC6") (class "Default")
      (node (ref "L2-BUTTONS-IN1-8") (pin "6") (pinfunction "6_6") (pintype "passive"))
      (node (ref "U$3") (pin "J4-35") (pinfunction "PC6_J4-35") (pintype "bidirectional"))
    )
    (net (code "58") (name "/L2-PC7") (class "Default")
      (node (ref "L2-BUTTONS-IN1-8") (pin "7") (pinfunction "7_7") (pintype "passive"))
      (node (ref "U$3") (pin "J4-34") (pinfunction "PC7_J4-34") (pintype "bidirectional"))
    )
    (net (code "59") (name "/L2-PD1") (class "Default")
      (node (ref "U$3") (pin "J3-24") (pinfunction "PD1_J3-24") (pintype "bidirectional"))
      (node (ref "ULN2") (pin "2") (pinfunction "IN_2_2") (pintype "bidirectional"))
    )
    (net (code "60") (name "/L2-PD2") (class "Default")
      (node (ref "U$3") (pin "J3-25") (pinfunction "PD2_J3-25") (pintype "bidirectional"))
      (node (ref "ULN2") (pin "3") (pinfunction "IN_3_3") (pintype "bidirectional"))
    )
    (net (code "61") (name "/L2-PD3") (class "Default")
      (node (ref "U$3") (pin "J3-26") (pinfunction "PD3_J3-26") (pintype "bidirectional"))
      (node (ref "ULN2") (pin "4") (pinfunction "IN_4_4") (pintype "bidirectional"))
    )
    (net (code "62") (name "/L2-PD6") (class "Default")
      (node (ref "L2-BUTTONS-IN1-8") (pin "8") (pinfunction "8_8") (pintype "passive"))
      (node (ref "U$3") (pin "J4-33") (pinfunction "PD6_J4-33") (pintype "bidirectional"))
    )
    (net (code "63") (name "/L2-PD7") (class "Default")
      (node (ref "L2-BUTTONS-IN9-16") (pin "1") (pinfunction "1_1") (pintype "passive"))
      (node (ref "U$3") (pin "J4-32") (pinfunction "PD7_J4-32") (pintype "bidirectional"))
    )
    (net (code "64") (name "/L2-PE1") (class "Default")
      (node (ref "U$3") (pin "J3-27") (pinfunction "PE1_J3-27") (pintype "bidirectional"))
      (node (ref "ULN2") (pin "5") (pinfunction "IN_5_5") (pintype "bidirectional"))
    )
    (net (code "65") (name "/L2-PE2") (class "Default")
      (node (ref "U$3") (pin "J3-28") (pinfunction "PE2_J3-28") (pintype "bidirectional"))
      (node (ref "ULN2") (pin "6") (pinfunction "IN_6_6") (pintype "bidirectional"))
    )
    (net (code "66") (name "/L2-PE3") (class "Default")
      (node (ref "U$3") (pin "J3-29") (pinfunction "PE3_J3-29") (pintype "bidirectional"))
      (node (ref "ULN2") (pin "7") (pinfunction "IN_7_7") (pintype "bidirectional"))
    )
    (net (code "67") (name "/L2-PE4") (class "Default")
      (node (ref "U$3") (pin "J1-5") (pinfunction "PE4_J1-5") (pintype "bidirectional"))
      (node (ref "ULN1") (pin "4") (pinfunction "IN_4_4") (pintype "bidirectional"))
    )
    (net (code "68") (name "/L2-PE5") (class "Default")
      (node (ref "U$3") (pin "J1-6") (pinfunction "PE5_J1-6") (pintype "bidirectional"))
      (node (ref "ULN1") (pin "5") (pinfunction "IN_5_5") (pintype "bidirectional"))
    )
    (net (code "69") (name "/L2-PF0") (class "Default")
      (node (ref "L2-BUTTONS-IN9-16") (pin "3") (pinfunction "3_3") (pintype "passive"))
      (node (ref "U$3") (pin "J2-17") (pinfunction "PF0_J2-17") (pintype "bidirectional"))
    )
    (net (code "70") (name "/L2-PF1") (class "Default")
      (node (ref "U$3") (pin "J3-30") (pinfunction "PF1_J3-30") (pintype "bidirectional"))
      (node (ref "ULN2") (pin "8") (pinfunction "IN_8_8") (pintype "bidirectional"))
    )
    (net (code "71") (name "/L2-PF2") (class "Default")
      (node (ref "L2-BUTTONS-IN1-8") (pin "1") (pinfunction "1_1") (pintype "passive"))
      (node (ref "U$3") (pin "J4-40") (pinfunction "PF2_J4-40") (pintype "bidirectional"))
    )
    (net (code "72") (name "/L2-PF3") (class "Default")
      (node (ref "L2-BUTTONS-IN1-8") (pin "2") (pinfunction "2_2") (pintype "passive"))
      (node (ref "U$3") (pin "J4-39") (pinfunction "PF3_J4-39") (pintype "bidirectional"))
    )
    (net (code "73") (name "/L2-PF4") (class "Default")
      (node (ref "L2-BUTTONS-IN9-16") (pin "2") (pinfunction "2_2") (pintype "passive"))
      (node (ref "U$3") (pin "J4-31") (pinfunction "PF4_J4-31") (pintype "bidirectional"))
    )
    (net (code "74") (name "/LED1-TO-RESISTOR") (class "Default")
      (node (ref "LEDS1-8") (pin "1") (pinfunction "1_1") (pintype "passive"))
      (node (ref "R21") (pin "2") (pinfunction "2_2") (pintype "passive"))
    )
    (net (code "75") (name "/LED2-TO-RESISTOR") (class "Default")
      (node (ref "LEDS1-8") (pin "3") (pinfunction "3_3") (pintype "passive"))
      (node (ref "R22") (pin "2") (pinfunction "2_2") (pintype "passive"))
    )
    (net (code "76") (name "/LED3-TO-RESISTOR") (class "Default")
      (node (ref "LEDS1-8") (pin "5") (pinfunction "5_5") (pintype "passive"))
      (node (ref "R23") (pin "2") (pinfunction "2_2") (pintype "passive"))
    )
    (net (code "77") (name "/LED4-TO-RESISTOR") (class "Default")
      (node (ref "LEDS1-8") (pin "7") (pinfunction "7_7") (pintype "passive"))
      (node (ref "R24") (pin "2") (pinfunction "2_2") (pintype "passive"))
    )
    (net (code "78") (name "/LED5-TO-RESISTOR") (class "Default")
      (node (ref "LEDS1-8") (pin "9") (pinfunction "9_9") (pintype "passive"))
      (node (ref "R25") (pin "2") (pinfunction "2_2") (pintype "passive"))
    )
    (net (code "79") (name "/LED6-TO-RESISTOR") (class "Default")
      (node (ref "LEDS1-8") (pin "11") (pinfunction "11_11") (pintype "passive"))
      (node (ref "R26") (pin "2") (pinfunction "2_2") (pintype "passive"))
    )
    (net (code "80") (name "/LED7-TO-RESISTOR") (class "Default")
      (node (ref "LEDS1-8") (pin "13") (pinfunction "13_13") (pintype "passive"))
      (node (ref "R27") (pin "2") (pinfunction "2_2") (pintype "passive"))
    )
    (net (code "81") (name "/LED8-TO-RESISTOR") (class "Default")
      (node (ref "LEDS1-8") (pin "15") (pinfunction "15_15") (pintype "passive"))
      (node (ref "R28") (pin "2") (pinfunction "2_2") (pintype "passive"))
    )
    (net (code "82") (name "/LED9-TO-RESISTOR") (class "Default")
      (node (ref "LEDS9-16") (pin "1") (pinfunction "1_1") (pintype "passive"))
      (node (ref "R29") (pin "2") (pinfunction "2_2") (pintype "passive"))
    )
    (net (code "83") (name "/LED10-TO-RESISTOR") (class "Default")
      (node (ref "LEDS9-16") (pin "3") (pinfunction "3_3") (pintype "passive"))
      (node (ref "R30") (pin "2") (pinfunction "2_2") (pintype "passive"))
    )
    (net (code "84") (name "/LED11-TO-RESISTOR") (class "Default")
      (node (ref "LEDS9-16") (pin "5") (pinfunction "5_5") (pintype "passive"))
      (node (ref "R31") (pin "2") (pinfunction "2_2") (pintype "passive"))
    )
    (net (code "85") (name "/LED12-TO-RESISTOR") (class "Default")
      (node (ref "LEDS9-16") (pin "7") (pinfunction "7_7") (pintype "passive"))
      (node (ref "R32") (pin "2") (pinfunction "2_2") (pintype "passive"))
    )
    (net (code "86") (name "/LED13-TO-RESISTOR") (class "Default")
      (node (ref "LEDS9-16") (pin "9") (pinfunction "9_9") (pintype "passive"))
      (node (ref "R33") (pin "2") (pinfunction "2_2") (pintype "passive"))
    )
    (net (code "87") (name "/LED14-TO-RESISTOR") (class "Default")
      (node (ref "LEDS9-16") (pin "11") (pinfunction "11_11") (pintype "passive"))
      (node (ref "R34") (pin "2") (pinfunction "2_2") (pintype "passive"))
    )
    (net (code "88") (name "/LED15-TO-RESISTOR") (class "Default")
      (node (ref "LEDS9-16") (pin "13") (pinfunction "13_13") (pintype "passive"))
      (node (ref "R35") (pin "2") (pinfunction "2_2") (pintype "passive"))
    )
    (net (code "89") (name "/LED16-TO-RESISTOR") (class "Default")
      (node (ref "LEDS9-16") (pin "15") (pinfunction "15_15") (pintype "passive"))
      (node (ref "R36") (pin "2") (pinfunction "2_2") (pintype "passive"))
    )
    (net (code "90") (name "/MC34-INA") (class "Default")
      (node (ref "IC2") (pin "4") (pinfunction "IN_4") (pintype "input"))
      (node (ref "IC2-IN") (pin "TP") (pinfunction "TP_TP") (pintype "input"))
      (node (ref "R5") (pin "2") (pinfunction "2_2") (pintype "passive"))
      (node (ref "RF") (pin "1") (pinfunction "1_1") (pintype "passive"))
    )
    (net (code "91") (name "/MC34-INB") (class "Default")
      (node (ref "IC6") (pin "4") (pinfunction "IN_4") (pintype "input"))
      (node (ref "IC6-IN") (pin "TP") (pinfunction "TP_TP") (pintype "input"))
      (node (ref "R1") (pin "2") (pinfunction "2_2") (pintype "passive"))
      (node (ref "RF1") (pin "1") (pinfunction "1_1") (pintype "passive"))
    )
    (net (code "92") (name "/MC34-INPUT2") (class "Default")
      (node (ref "C2-TANTALUM") (pin "+") (pinfunction "+_+") (pintype "passive"))
      (node (ref "IC2") (pin "2") (pinfunction "FC2_2") (pintype "passive"))
    )
    (net (code "93") (name "/MC34-INPUT2B") (class "Default")
      (node (ref "C2-TANTALUMB") (pin "+") (pinfunction "+_+") (pintype "passive"))
      (node (ref "IC6") (pin "2") (pinfunction "FC2_2") (pintype "passive"))
    )
    (net (code "94") (name "/MC34-INPUT3") (class "Default")
      (node (ref "C3-TANTALUM") (pin "+") (pinfunction "+_+") (pintype "passive"))
      (node (ref "IC2") (pin "3") (pinfunction "FC1_3") (pintype "passive"))
    )
    (net (code "95") (name "/MC34-INPUT3B") (class "Default")
      (node (ref "C3-TANTALUMB") (pin "+") (pinfunction "+_+") (pintype "passive"))
      (node (ref "IC6") (pin "3") (pinfunction "FC1_3") (pintype "passive"))
    )
    (net (code "96") (name "/OUTA") (class "Default")
      (node (ref "C1-CERAMIC") (pin "1") (pinfunction "1_1") (pintype "passive"))
      (node (ref "IC5") (pin "4") (pinfunction "OUTA_4") (pintype "bidirectional"))
    )
    (net (code "97") (name "/OUTB") (class "Default")
      (node (ref "C1-CERAMIC1") (pin "1") (pinfunction "1_1") (pintype "passive"))
      (node (ref "IC5") (pin "7") (pinfunction "OUTB_7") (pintype "bidirectional"))
    )
    (net (code "98") (name "/POT-TO-RESISTOR_DAC-TO-OP-AMPA") (class "Default")
      (node (ref "C1-CERAMIC") (pin "2") (pinfunction "2_2") (pintype "passive"))
      (node (ref "R5") (pin "1") (pinfunction "1_1") (pintype "passive"))
    )
    (net (code "99") (name "/POT-TO-RESISTOR_DAC-TO-OP-AMPB") (class "Default")
      (node (ref "C1-CERAMIC1") (pin "2") (pinfunction "2_2") (pintype "passive"))
      (node (ref "R1") (pin "1") (pinfunction "1_1") (pintype "passive"))
    )
    (net (code "100") (name "/R21-TO-ULN") (class "Default")
      (node (ref "R21") (pin "1") (pinfunction "1_1") (pintype "passive"))
      (node (ref "ULN1") (pin "18") (pinfunction "OUT_1_18") (pintype "bidirectional"))
    )
    (net (code "101") (name "/R22-TO-ULN") (class "Default")
      (node (ref "R22") (pin "1") (pinfunction "1_1") (pintype "passive"))
      (node (ref "ULN1") (pin "17") (pinfunction "OUT_2_17") (pintype "bidirectional"))
    )
    (net (code "102") (name "/R23-TO-ULN") (class "Default")
      (node (ref "R23") (pin "1") (pinfunction "1_1") (pintype "passive"))
      (node (ref "ULN1") (pin "16") (pinfunction "OUT_3_16") (pintype "bidirectional"))
    )
    (net (code "103") (name "/R24-TO-ULN") (class "Default")
      (node (ref "R24") (pin "1") (pinfunction "1_1") (pintype "passive"))
      (node (ref "ULN1") (pin "15") (pinfunction "OUT_4_15") (pintype "bidirectional"))
    )
    (net (code "104") (name "/R25-TO-ULN") (class "Default")
      (node (ref "R25") (pin "1") (pinfunction "1_1") (pintype "passive"))
      (node (ref "ULN1") (pin "14") (pinfunction "OUT_5_14") (pintype "bidirectional"))
    )
    (net (code "105") (name "/R26-TO-ULN") (class "Default")
      (node (ref "R26") (pin "1") (pinfunction "1_1") (pintype "passive"))
      (node (ref "ULN1") (pin "13") (pinfunction "OUT_6_13") (pintype "bidirectional"))
    )
    (net (code "106") (name "/R27-TO-ULN") (class "Default")
      (node (ref "R27") (pin "1") (pinfunction "1_1") (pintype "passive"))
      (node (ref "ULN1") (pin "12") (pinfunction "OUT_7_12") (pintype "bidirectional"))
    )
    (net (code "107") (name "/R28-TO-ULN") (class "Default")
      (node (ref "R28") (pin "1") (pinfunction "1_1") (pintype "passive"))
      (node (ref "ULN1") (pin "11") (pinfunction "OUT_8_11") (pintype "bidirectional"))
    )
    (net (code "108") (name "/R29-TO-ULN") (class "Default")
      (node (ref "R29") (pin "1") (pinfunction "1_1") (pintype "passive"))
      (node (ref "ULN2") (pin "18") (pinfunction "OUT_1_18") (pintype "bidirectional"))
    )
    (net (code "109") (name "/R30-TO-ULN") (class "Default")
      (node (ref "R30") (pin "1") (pinfunction "1_1") (pintype "passive"))
      (node (ref "ULN2") (pin "17") (pinfunction "OUT_2_17") (pintype "bidirectional"))
    )
    (net (code "110") (name "/R31-TO-ULN") (class "Default")
      (node (ref "R31") (pin "1") (pinfunction "1_1") (pintype "passive"))
      (node (ref "ULN2") (pin "16") (pinfunction "OUT_3_16") (pintype "bidirectional"))
    )
    (net (code "111") (name "/R32-TO-ULN") (class "Default")
      (node (ref "R32") (pin "1") (pinfunction "1_1") (pintype "passive"))
      (node (ref "ULN2") (pin "15") (pinfunction "OUT_4_15") (pintype "bidirectional"))
    )
    (net (code "112") (name "/R33-TO-ULN") (class "Default")
      (node (ref "R33") (pin "1") (pinfunction "1_1") (pintype "passive"))
      (node (ref "ULN2") (pin "14") (pinfunction "OUT_5_14") (pintype "bidirectional"))
    )
    (net (code "113") (name "/R34-TO-ULN") (class "Default")
      (node (ref "R34") (pin "1") (pinfunction "1_1") (pintype "passive"))
      (node (ref "ULN2") (pin "13") (pinfunction "OUT_6_13") (pintype "bidirectional"))
    )
    (net (code "114") (name "/R35-TO-ULN") (class "Default")
      (node (ref "R35") (pin "1") (pinfunction "1_1") (pintype "passive"))
      (node (ref "ULN2") (pin "12") (pinfunction "OUT_7_12") (pintype "bidirectional"))
    )
    (net (code "115") (name "/R36-TO-ULN") (class "Default")
      (node (ref "R36") (pin "1") (pinfunction "1_1") (pintype "passive"))
      (node (ref "ULN2") (pin "11") (pinfunction "OUT_8_11") (pintype "bidirectional"))
    )
    (net (code "116") (name "/RING") (class "Default")
      (node (ref "AUDIO-JACK-CONNECTOR") (pin "3") (pinfunction "3_3") (pintype "passive"))
      (node (ref "JP1") (pin "1") (pinfunction "RING_1") (pintype "passive"))
    )
    (net (code "117") (name "/TIP") (class "Default")
      (node (ref "AUDIO-JACK-CONNECTOR") (pin "2") (pinfunction "2_2") (pintype "passive"))
      (node (ref "JP1") (pin "2") (pinfunction "TIP_2") (pintype "passive"))
    )
    (net (code "118") (name "/TO-SPEAKER-INPUT-1A") (class "Default")
      (node (ref "IC2") (pin "5") (pinfunction "VO1_5") (pintype "output"))
      (node (ref "RF") (pin "2") (pinfunction "2_2") (pintype "passive"))
      (node (ref "SP1") (pin "1") (pinfunction "1_1") (pintype "passive"))
    )
    (net (code "119") (name "/TO-SPEAKER-INPUT-1B") (class "Default")
      (node (ref "IC6") (pin "5") (pinfunction "VO1_5") (pintype "output"))
      (node (ref "RF1") (pin "2") (pinfunction "2_2") (pintype "passive"))
      (node (ref "SP2") (pin "1") (pinfunction "1_1") (pintype "passive"))
    )
    (net (code "120") (name "/TO-SPEAKER-INPUT-2A") (class "Default")
      (node (ref "IC2") (pin "8") (pinfunction "VO2_8") (pintype "output"))
      (node (ref "SP1") (pin "2") (pinfunction "2_2") (pintype "passive"))
    )
    (net (code "121") (name "/TO-SPEAKER-INPUT-2B") (class "Default")
      (node (ref "IC6") (pin "8") (pinfunction "VO2_8") (pintype "output"))
      (node (ref "SP2") (pin "2") (pinfunction "2_2") (pintype "passive"))
    )
    (net (code "122") (name "/VBUS-SUPPLY") (class "Default")
      (node (ref "C6") (pin "1") (pinfunction "1_1") (pintype "passive"))
      (node (ref "CS") (pin "1") (pinfunction "1_1") (pintype "passive"))
      (node (ref "CS1") (pin "1") (pinfunction "1_1") (pintype "passive"))
      (node (ref "IC2") (pin "6") (pinfunction "VCC_6") (pintype "power_in"))
      (node (ref "IC6") (pin "6") (pinfunction "VCC_6") (pintype "power_in"))
      (node (ref "PS1") (pin "3") (pinfunction "OUTPUT_3") (pintype "output"))
      (node (ref "U$2") (pin "J3-21") (pinfunction "+5.0V_J3-21") (pintype "bidirectional"))
      (node (ref "U$3") (pin "J3-21") (pinfunction "+5.0V_J3-21") (pintype "bidirectional"))
      (node (ref "VBUS-5V") (pin "TP") (pinfunction "TP_TP") (pintype "input"))
    )
    (net (code "123") (name "GND") (class "Default")
      (node (ref "5V-LED-GND") (pin "TP") (pinfunction "TP_TP") (pintype "input"))
      (node (ref "BJ-GND") (pin "TP") (pinfunction "TP_TP") (pintype "input"))
      (node (ref "C1") (pin "-") (pinfunction "-_-") (pintype "passive"))
      (node (ref "C19") (pin "1") (pinfunction "1_1") (pintype "passive"))
      (node (ref "C2") (pin "2") (pinfunction "2_2") (pintype "passive"))
      (node (ref "C2-TANTALUM") (pin "-") (pinfunction "-_-") (pintype "passive"))
      (node (ref "C2-TANTALUMB") (pin "-") (pinfunction "-_-") (pintype "passive"))
      (node (ref "C3") (pin "-") (pinfunction "-_-") (pintype "passive"))
      (node (ref "C3-TANTALUM") (pin "-") (pinfunction "-_-") (pintype "passive"))
      (node (ref "C3-TANTALUMB") (pin "-") (pinfunction "-_-") (pintype "passive"))
      (node (ref "C4") (pin "-") (pinfunction "-_-") (pintype "passive"))
      (node (ref "C5") (pin "-") (pinfunction "-_-") (pintype "passive"))
      (node (ref "C6") (pin "2") (pinfunction "2_2") (pintype "passive"))
      (node (ref "C7") (pin "2") (pinfunction "2_2") (pintype "passive"))
      (node (ref "C8") (pin "2") (pinfunction "2_2") (pintype "passive"))
      (node (ref "C9") (pin "-") (pinfunction "-_-") (pintype "passive"))
      (node (ref "CS") (pin "2") (pinfunction "2_2") (pintype "passive"))
      (node (ref "CS1") (pin "2") (pinfunction "2_2") (pintype "passive"))
      (node (ref "DAC-GND") (pin "TP") (pinfunction "TP_TP") (pintype "input"))
      (node (ref "IC1") (pin "3") (pinfunction "A_3") (pintype "passive"))
      (node (ref "IC2") (pin "1") (pinfunction "CD_1") (pintype "passive"))
      (node (ref "IC2") (pin "7") (pinfunction "GND_7") (pintype "power_in"))
      (node (ref "IC3") (pin "2") (pinfunction "GND_2") (pintype "passive"))
      (node (ref "IC4") (pin "2") (pinfunction "GND_2") (pintype "power_in"))
      (node (ref "IC5") (pin "5") (pinfunction "AGND_5") (pintype "bidirectional"))
      (node (ref "IC6") (pin "1") (pinfunction "CD_1") (pintype "passive"))
      (node (ref "IC6") (pin "7") (pinfunction "GND_7") (pintype "power_in"))
      (node (ref "J1") (pin "2") (pinfunction "2_2") (pintype "bidirectional"))
      (node (ref "LCD-GND") (pin "TP") (pinfunction "TP_TP") (pintype "input"))
      (node (ref "POWER-BOARD-JUMPER") (pin "2") (pinfunction "2_2") (pintype "passive"))
      (node (ref "PS1") (pin "2") (pinfunction "GND_2") (pintype "power_in"))
      (node (ref "R2") (pin "1") (pinfunction "1_1") (pintype "passive"))
      (node (ref "ROUND-POT-VOLULME") (pin "3") (pinfunction "3_3") (pintype "passive"))
      (node (ref "SLIDE-POT-TONE") (pin "3") (pinfunction "3_3") (pintype "passive"))
      (node (ref "ST7735LCD") (pin "1") (pinfunction "1_1") (pintype "passive"))
      (node (ref "U$1") (pin "GND") (pinfunction "1-GND_GND") (pintype "bidirectional"))
      (node (ref "U$2") (pin "J2-20") (pinfunction "GND2_J2-20") (pintype "bidirectional"))
      (node (ref "U$2") (pin "J3-22") (pinfunction "GND1_J3-22") (pintype "bidirectional"))
      (node (ref "U$3") (pin "J2-20") (pinfunction "GND2_J2-20") (pintype "bidirectional"))
      (node (ref "U$3") (pin "J3-22") (pinfunction "GND1_J3-22") (pintype "bidirectional"))
      (node (ref "ULN1") (pin "9") (pinfunction "GND_9") (pintype "bidirectional"))
      (node (ref "ULN1-GND") (pin "TP") (pinfunction "TP_TP") (pintype "input"))
      (node (ref "ULN2") (pin "9") (pinfunction "GND_9") (pintype "bidirectional"))
      (node (ref "ULN2-GND") (pin "TP") (pinfunction "TP_TP") (pintype "input"))
    )
    (net (code "124") (name "unconnected-(J1-Pad3)") (class "Default")
      (node (ref "J1") (pin "3") (pinfunction "3_3") (pintype "bidirectional"))
    )
    (net (code "125") (name "unconnected-(U$2B-PB4-PadJ1-7)") (class "Default")
      (node (ref "U$2") (pin "J1-7") (pinfunction "PB4_J1-7") (pintype "bidirectional"))
    )
    (net (code "126") (name "unconnected-(U$2D-PD7-PadJ4-32)") (class "Default")
      (node (ref "U$2") (pin "J4-32") (pinfunction "PD7_J4-32") (pintype "bidirectional"))
    )
    (net (code "127") (name "unconnected-(U$2G-+3.3V-PadJ1-1)") (class "Default")
      (node (ref "U$2") (pin "J1-1") (pinfunction "+3.3V_J1-1") (pintype "bidirectional"))
    )
    (net (code "128") (name "unconnected-(U$2G-RESET-PadJ2-16)") (class "Default")
      (node (ref "U$2") (pin "J2-16") (pinfunction "RESET_J2-16") (pintype "bidirectional"))
    )
    (net (code "129") (name "unconnected-(U$3B-PB2-PadJ2-19)") (class "Default")
      (node (ref "U$3") (pin "J2-19") (pinfunction "PB2_J2-19") (pintype "bidirectional"))
    )
    (net (code "130") (name "unconnected-(U$3D-PD0-PadJ3-23)") (class "Default")
      (node (ref "U$3") (pin "J3-23") (pinfunction "PD0_J3-23") (pintype "bidirectional"))
    )
    (net (code "131") (name "unconnected-(U$3E-PE0-PadJ2-18)") (class "Default")
      (node (ref "U$3") (pin "J2-18") (pinfunction "PE0_J2-18") (pintype "bidirectional"))
    )
    (net (code "132") (name "unconnected-(U$3G-+3.3V-PadJ1-1)") (class "Default")
      (node (ref "U$3") (pin "J1-1") (pinfunction "+3.3V_J1-1") (pintype "bidirectional"))
    )
    (net (code "133") (name "unconnected-(U$3G-RESET-PadJ2-16)") (class "Default")
      (node (ref "U$3") (pin "J2-16") (pinfunction "RESET_J2-16") (pintype "bidirectional"))
    )
    (net (code "134") (name "unconnected-(ULN1-COMMON_FREE__WHEELING_DIODES-Pad10)") (class "Default")
      (node (ref "ULN1") (pin "10") (pinfunction "COMMON_FREE__WHEELING_DIODES_10") (pintype "bidirectional"))
    )
    (net (code "135") (name "unconnected-(ULN2-COMMON_FREE__WHEELING_DIODES-Pad10)") (class "Default")
      (node (ref "ULN2") (pin "10") (pinfunction "COMMON_FREE__WHEELING_DIODES_10") (pintype "bidirectional"))
    )
  )
)
